# pretinhaMonitorBoard.net
KiCad netlist of a schematic drawn in EAGLE
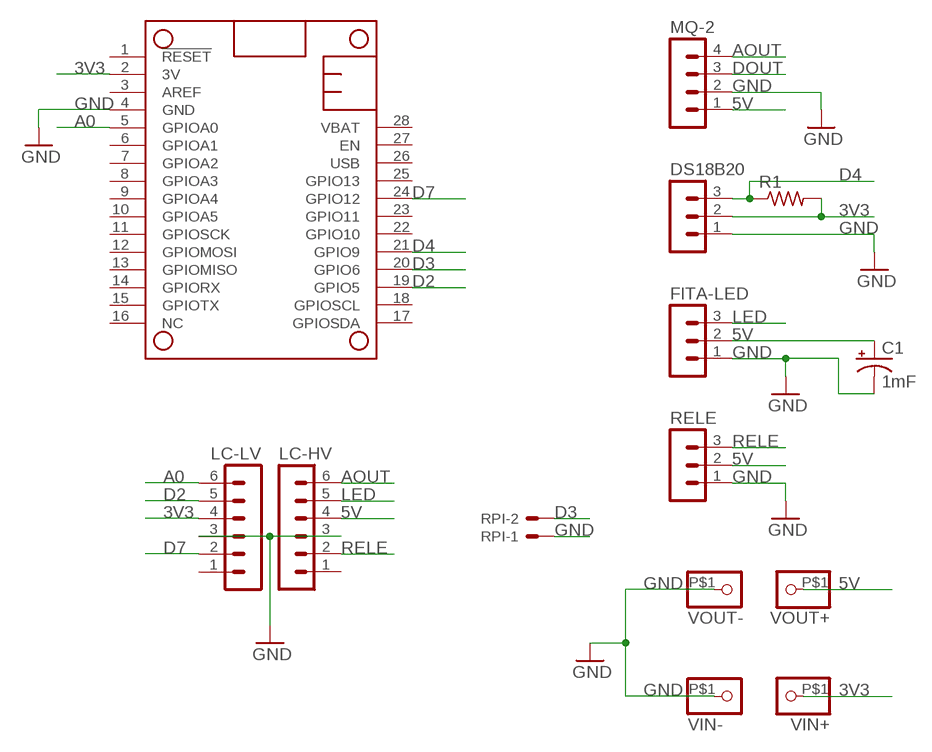
[diagram p0: schematic, sheet 1]

(export (version "E")
  (design (tool "Eeschema 10.0.6"))
  (components
    (comp (ref "C1")
      (value "1mF")
      (footprint "eagle-import:CPOL-RADIAL-5MM-10MM")
      (libsource (lib "eagle-import") (part "1000UF-RADIAL-5MM-25V-20%"))
    )
    (comp (ref "DS18B20")
      (value "MA03-1")
      (footprint "eagle-import:MA03-1")
      (libsource (lib "eagle-import") (part "MA03-1"))
    )
    (comp (ref "FITA-LED")
      (value "MA03-1")
      (footprint "eagle-import:MA03-1")
      (libsource (lib "eagle-import") (part "MA03-1"))
    )
    (comp (ref "LC-HV")
      (value "MA06-1")
      (footprint "eagle-import:MA06-1")
      (libsource (lib "eagle-import") (part "MA06-1"))
    )
    (comp (ref "LC-LV")
      (value "MA06-1")
      (footprint "eagle-import:MA06-1")
      (libsource (lib "eagle-import") (part "MA06-1"))
    )
    (comp (ref "MESH")
      (value "FEATHERWING_NODIM")
      (footprint "eagle-import:FEATHERWING_DIM")
      (libsource (lib "eagle-import") (part "FEATHERWING_NODIM"))
    )
    (comp (ref "MQ-2")
      (value "MA04-1")
      (footprint "eagle-import:MA04-1")
      (libsource (lib "eagle-import") (part "MA04-1"))
    )
    (comp (ref "R1")
      (value "R-US_0411/15")
      (footprint "eagle-import:0411_15")
      (libsource (lib "eagle-import") (part "R-US_0411/15"))
    )
    (comp (ref "RELE")
      (value "MA03-1")
      (footprint "eagle-import:MA03-1")
      (libsource (lib "eagle-import") (part "MA03-1"))
    )
    (comp (ref "RPI")
      (value "22-23-2021")
      (footprint "eagle-import:22-23-2021")
      (fields (field (name "MF") "MOLEX"))
      (libsource (lib "eagle-import") (part "22-23-2021"))
    )
    (comp (ref "VIN+")
      (value "PINHD-1X1-BIGPOGO")
      (footprint "eagle-import:1X1-BIGPOGO")
      (libsource (lib "eagle-import") (part "PINHD-1X1-BIGPOGO"))
    )
    (comp (ref "VIN-")
      (value "PINHD-1X1-BIGPOGO")
      (footprint "eagle-import:1X1-BIGPOGO")
      (libsource (lib "eagle-import") (part "PINHD-1X1-BIGPOGO"))
    )
    (comp (ref "VOUT+")
      (value "PINHD-1X1-BIGPOGO")
      (footprint "eagle-import:1X1-BIGPOGO")
      (libsource (lib "eagle-import") (part "PINHD-1X1-BIGPOGO"))
    )
    (comp (ref "VOUT-")
      (value "PINHD-1X1-BIGPOGO")
      (footprint "eagle-import:1X1-BIGPOGO")
      (libsource (lib "eagle-import") (part "PINHD-1X1-BIGPOGO"))
    )
  )
  (nets
    (net (code "1") (name "/3V3") (class "Default")
      (node (ref "DS18B20") (pin "2") (pinfunction "2_2") (pintype "passive"))
      (node (ref "LC-LV") (pin "4") (pinfunction "4_4") (pintype "passive"))
      (node (ref "MESH") (pin "2") (pinfunction "3V_2") (pintype "power_in"))
      (node (ref "R1") (pin "2") (pinfunction "2_2") (pintype "passive"))
      (node (ref "VIN+") (pin "P$1") (pinfunction "1_P$1") (pintype "passive"))
    )
    (net (code "2") (name "/5V") (class "Default")
      (node (ref "C1") (pin "+") (pinfunction "+_+") (pintype "passive"))
      (node (ref "FITA-LED") (pin "2") (pinfunction "2_2") (pintype "passive"))
      (node (ref "LC-HV") (pin "4") (pinfunction "4_4") (pintype "passive"))
      (node (ref "MQ-2") (pin "1") (pinfunction "1_1") (pintype "passive"))
      (node (ref "RELE") (pin "2") (pinfunction "2_2") (pintype "passive"))
      (node (ref "VOUT+") (pin "P$1") (pinfunction "1_P$1") (pintype "passive"))
    )
    (net (code "3") (name "/A0") (class "Default")
      (node (ref "LC-LV") (pin "6") (pinfunction "6_6") (pintype "passive"))
      (node (ref "MESH") (pin "5") (pinfunction "GPIOA0_5") (pintype "bidirectional"))
    )
    (net (code "4") (name "/AOUT") (class "Default")
      (node (ref "LC-HV") (pin "6") (pinfunction "6_6") (pintype "passive"))
      (node (ref "MQ-2") (pin "4") (pinfunction "4_4") (pintype "passive"))
    )
    (net (code "5") (name "/D2") (class "Default")
      (node (ref "LC-LV") (pin "5") (pinfunction "5_5") (pintype "passive"))
      (node (ref "MESH") (pin "19") (pinfunction "GPIO5_19") (pintype "bidirectional"))
    )
    (net (code "6") (name "/D3") (class "Default")
      (node (ref "MESH") (pin "20") (pinfunction "GPIO6_20") (pintype "bidirectional"))
      (node (ref "RPI") (pin "2") (pinfunction "S_2") (pintype "passive"))
    )
    (net (code "7") (name "/D4") (class "Default")
      (node (ref "DS18B20") (pin "3") (pinfunction "3_3") (pintype "passive"))
      (node (ref "MESH") (pin "21") (pinfunction "GPIO9_21") (pintype "bidirectional"))
      (node (ref "R1") (pin "1") (pinfunction "1_1") (pintype "passive"))
    )
    (net (code "8") (name "/D7") (class "Default")
      (node (ref "LC-LV") (pin "2") (pinfunction "2_2") (pintype "passive"))
      (node (ref "MESH") (pin "24") (pinfunction "GPIO12_24") (pintype "bidirectional"))
    )
    (net (code "9") (name "/DOUT") (class "Default")
      (node (ref "MQ-2") (pin "3") (pinfunction "3_3") (pintype "passive"))
    )
    (net (code "10") (name "/LED") (class "Default")
      (node (ref "FITA-LED") (pin "3") (pinfunction "3_3") (pintype "passive"))
      (node (ref "LC-HV") (pin "5") (pinfunction "5_5") (pintype "passive"))
    )
    (net (code "11") (name "/RELE") (class "Default")
      (node (ref "LC-HV") (pin "2") (pinfunction "2_2") (pintype "passive"))
      (node (ref "RELE") (pin "3") (pinfunction "3_3") (pintype "passive"))
    )
    (net (code "12") (name "/USB") (class "Default")
      (node (ref "MESH") (pin "26") (pinfunction "USB_26") (pintype "power_in"))
    )
    (net (code "13") (name "/VBAT") (class "Default")
      (node (ref "MESH") (pin "28") (pinfunction "VBAT_28") (pintype "power_in"))
    )
    (net (code "14") (name "GND") (class "Default")
      (node (ref "C1") (pin "-") (pinfunction "-_-") (pintype "passive"))
      (node (ref "DS18B20") (pin "1") (pinfunction "1_1") (pintype "passive"))
      (node (ref "FITA-LED") (pin "1") (pinfunction "1_1") (pintype "passive"))
      (node (ref "LC-HV") (pin "3") (pinfunction "3_3") (pintype "passive"))
      (node (ref "LC-LV") (pin "3") (pinfunction "3_3") (pintype "passive"))
      (node (ref "MESH") (pin "4") (pinfunction "GND_4") (pintype "power_in"))
      (node (ref "MQ-2") (pin "2") (pinfunction "2_2") (pintype "passive"))
      (node (ref "RELE") (pin "1") (pinfunction "1_1") (pintype "passive"))
      (node (ref "RPI") (pin "1") (pinfunction "S_1") (pintype "passive"))
      (node (ref "VIN-") (pin "P$1") (pinfunction "1_P$1") (pintype "passive"))
      (node (ref "VOUT-") (pin "P$1") (pinfunction "1_P$1") (pintype "passive"))
    )
    (net (code "15") (name "unconnected-(LC-HV-Pad1)") (class "Default")
      (node (ref "LC-HV") (pin "1") (pinfunction "1_1") (pintype "passive"))
    )
    (net (code "16") (name "unconnected-(LC-LV-Pad1)") (class "Default")
      (node (ref "LC-LV") (pin "1") (pinfunction "1_1") (pintype "passive"))
    )
    (net (code "17") (name "unconnected-(MESH-AREF-Pad3)") (class "Default")
      (node (ref "MESH") (pin "3") (pinfunction "AREF_3") (pintype "passive"))
    )
    (net (code "18") (name "unconnected-(MESH-EN-Pad27)") (class "Default")
      (node (ref "MESH") (pin "27") (pinfunction "EN_27") (pintype "passive"))
    )
    (net (code "19") (name "unconnected-(MESH-GPIO10-Pad22)") (class "Default")
      (node (ref "MESH") (pin "22") (pinfunction "GPIO10_22") (pintype "bidirectional"))
    )
    (net (code "20") (name "unconnected-(MESH-GPIO11-Pad23)") (class "Default")
      (node (ref "MESH") (pin "23") (pinfunction "GPIO11_23") (pintype "bidirectional"))
    )
    (net (code "21") (name "unconnected-(MESH-GPIO13-Pad25)") (class "Default")
      (node (ref "MESH") (pin "25") (pinfunction "GPIO13_25") (pintype "bidirectional"))
    )
    (net (code "22") (name "unconnected-(MESH-GPIOA1-Pad6)") (class "Default")
      (node (ref "MESH") (pin "6") (pinfunction "GPIOA1_6") (pintype "bidirectional"))
    )
    (net (code "23") (name "unconnected-(MESH-GPIOA2-Pad7)") (class "Default")
      (node (ref "MESH") (pin "7") (pinfunction "GPIOA2_7") (pintype "bidirectional"))
    )
    (net (code "24") (name "unconnected-(MESH-GPIOA3-Pad8)") (class "Default")
      (node (ref "MESH") (pin "8") (pinfunction "GPIOA3_8") (pintype "bidirectional"))
    )
    (net (code "25") (name "unconnected-(MESH-GPIOA4-Pad9)") (class "Default")
      (node (ref "MESH") (pin "9") (pinfunction "GPIOA4_9") (pintype "bidirectional"))
    )
    (net (code "26") (name "unconnected-(MESH-GPIOA5-Pad10)") (class "Default")
      (node (ref "MESH") (pin "10") (pinfunction "GPIOA5_10") (pintype "bidirectional"))
    )
    (net (code "27") (name "unconnected-(MESH-GPIOMISO-Pad13)") (class "Default")
      (node (ref "MESH") (pin "13") (pinfunction "GPIOMISO_13") (pintype "bidirectional"))
    )
    (net (code "28") (name "unconnected-(MESH-GPIOMOSI-Pad12)") (class "Default")
      (node (ref "MESH") (pin "12") (pinfunction "GPIOMOSI_12") (pintype "bidirectional"))
    )
    (net (code "29") (name "unconnected-(MESH-GPIORX-Pad14)") (class "Default")
      (node (ref "MESH") (pin "14") (pinfunction "GPIORX_14") (pintype "bidirectional"))
    )
    (net (code "30") (name "unconnected-(MESH-GPIOSCK-Pad11)") (class "Default")
      (node (ref "MESH") (pin "11") (pinfunction "GPIOSCK_11") (pintype "bidirectional"))
    )
    (net (code "31") (name "unconnected-(MESH-GPIOSCL-Pad18)") (class "Default")
      (node (ref "MESH") (pin "18") (pinfunction "GPIOSCL_18") (pintype "bidirectional"))
    )
    (net (code "32") (name "unconnected-(MESH-GPIOSDA-Pad17)") (class "Default")
      (node (ref "MESH") (pin "17") (pinfunction "GPIOSDA_17") (pintype "bidirectional"))
    )
    (net (code "33") (name "unconnected-(MESH-GPIOTX-Pad15)") (class "Default")
      (node (ref "MESH") (pin "15") (pinfunction "GPIOTX_15") (pintype "bidirectional"))
    )
    (net (code "34") (name "unconnected-(MESH-NC-Pad16)") (class "Default")
      (node (ref "MESH") (pin "16") (pinfunction "NC_16") (pintype "passive"))
    )
    (net (code "35") (name "unconnected-(MESH-~{RESET}-Pad1)") (class "Default")
      (node (ref "MESH") (pin "1") (pinfunction "~{RESET}_1") (pintype "input"))
    )
  )
)
